# Motorcontroller.net
KiCad netlist of a schematic drawn in EAGLE
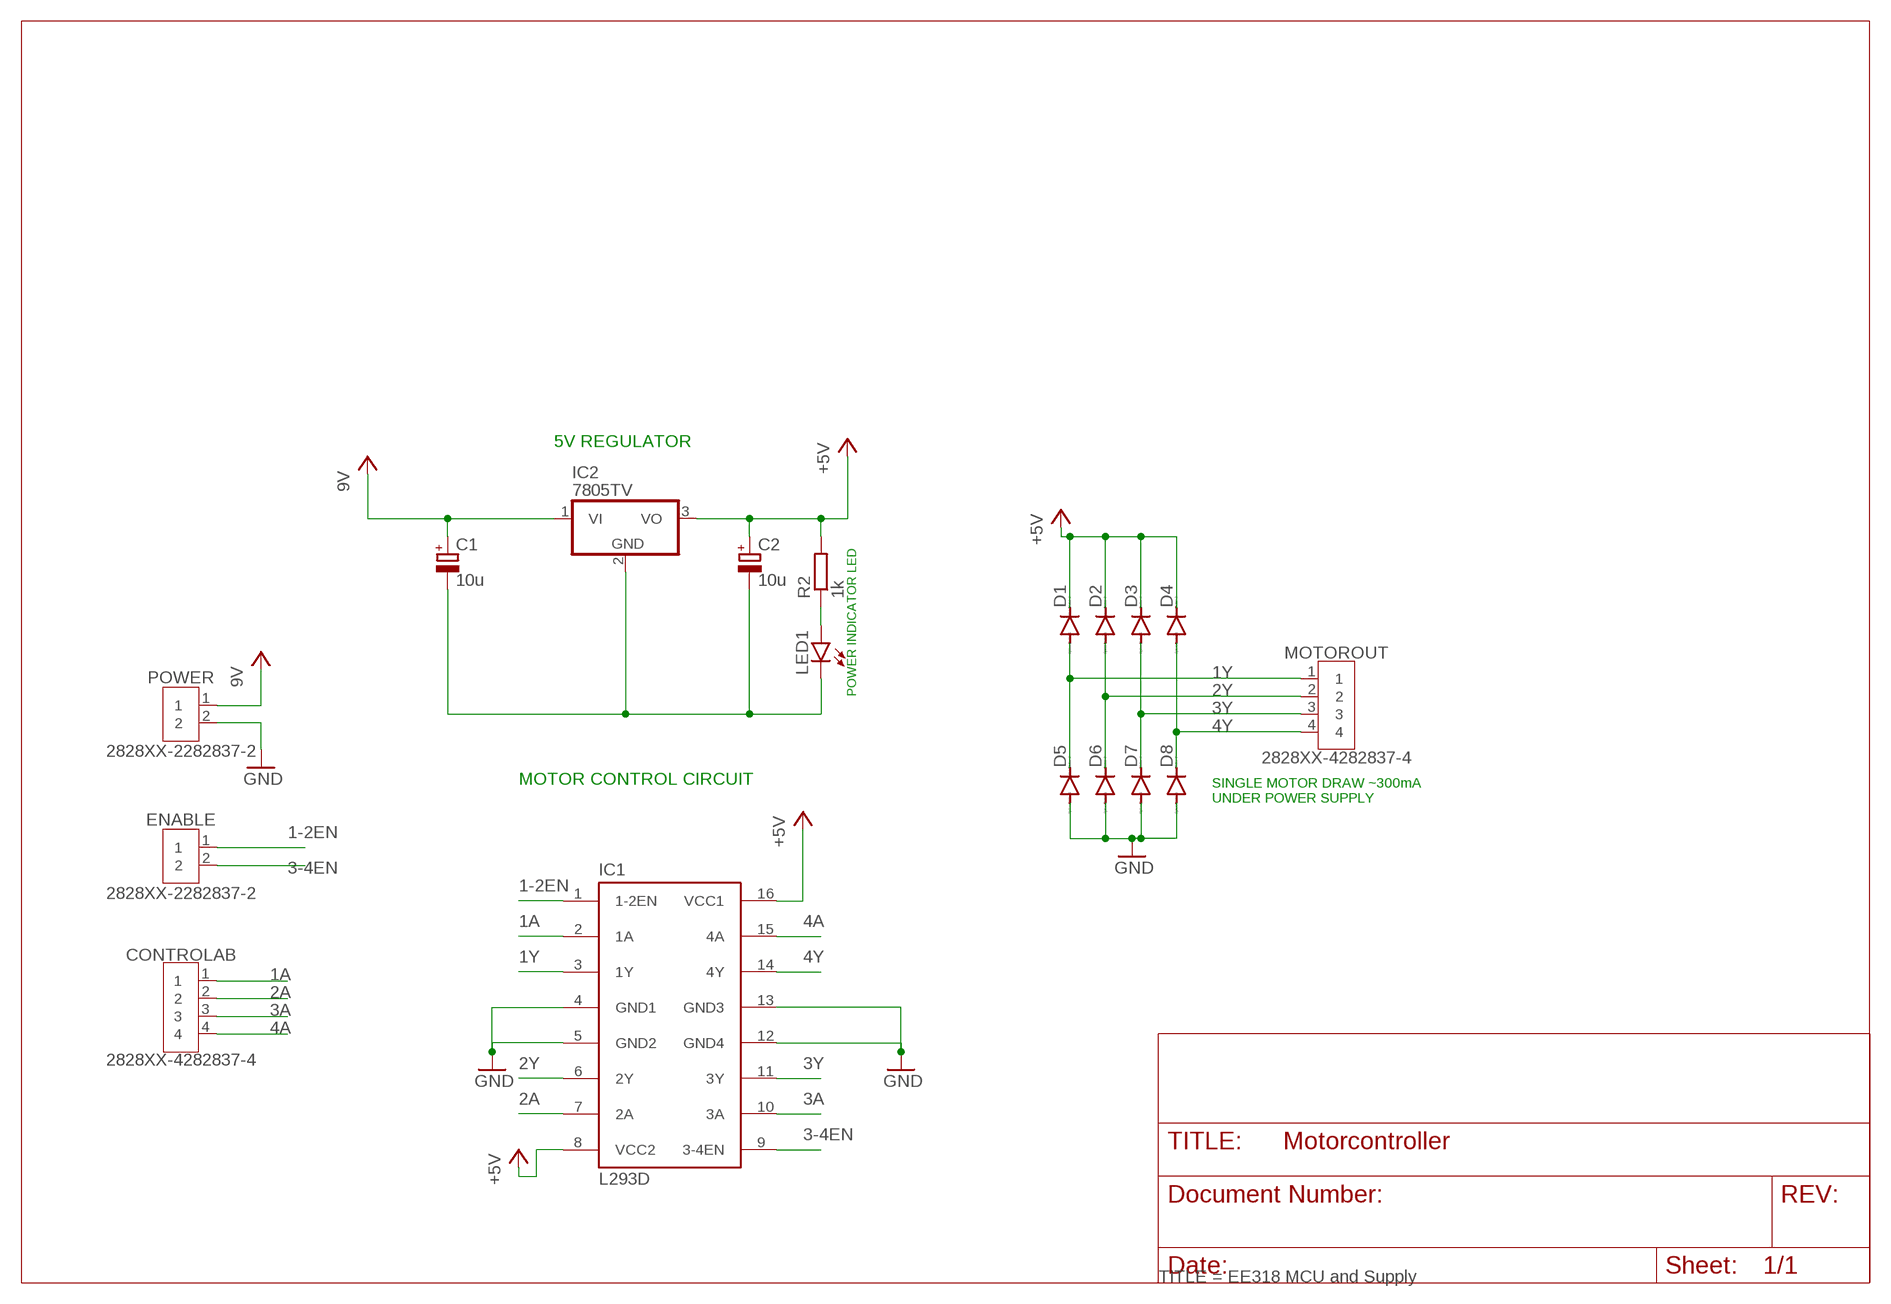
[diagram p0: schematic, sheet 1]

(export (version "E")
  (design (tool "Eeschema 10.0.6"))
  (components
    (comp (ref "C1")
      (value "10u")
      (footprint "eagle-import:E1,8-4")
      (libsource (lib "eagle-import") (part "CPOL-EUE1.8-4"))
    )
    (comp (ref "C2")
      (value "10u")
      (footprint "eagle-import:E1,8-4")
      (libsource (lib "eagle-import") (part "CPOL-EUE1.8-4"))
    )
    (comp (ref "CONTROLAB")
      (value "2828XX-4282837-4")
      (footprint "eagle-import:TERMBLK_508-4N")
      (fields (field (name "MANUFACTURER") "TE Connectivity AMP Connectors ") (field (name "MPN") "282837-4"))
      (libsource (lib "eagle-import") (part "2828XX-4282837-4"))
    )
    (comp (ref "D1")
      (value "DIODE-DO214AC")
      (footprint "eagle-import:DO214AC")
      (libsource (lib "eagle-import") (part "DIODE-DO214AC"))
    )
    (comp (ref "D2")
      (value "DIODE-DO214AC")
      (footprint "eagle-import:DO214AC")
      (libsource (lib "eagle-import") (part "DIODE-DO214AC"))
    )
    (comp (ref "D3")
      (value "DIODE-DO214AC")
      (footprint "eagle-import:DO214AC")
      (libsource (lib "eagle-import") (part "DIODE-DO214AC"))
    )
    (comp (ref "D4")
      (value "DIODE-DO214AC")
      (footprint "eagle-import:DO214AC")
      (libsource (lib "eagle-import") (part "DIODE-DO214AC"))
    )
    (comp (ref "D5")
      (value "DIODE-DO214AC")
      (footprint "eagle-import:DO214AC")
      (libsource (lib "eagle-import") (part "DIODE-DO214AC"))
    )
    (comp (ref "D6")
      (value "DIODE-DO214AC")
      (footprint "eagle-import:DO214AC")
      (libsource (lib "eagle-import") (part "DIODE-DO214AC"))
    )
    (comp (ref "D7")
      (value "DIODE-DO214AC")
      (footprint "eagle-import:DO214AC")
      (libsource (lib "eagle-import") (part "DIODE-DO214AC"))
    )
    (comp (ref "D8")
      (value "DIODE-DO214AC")
      (footprint "eagle-import:DO214AC")
      (libsource (lib "eagle-import") (part "DIODE-DO214AC"))
    )
    (comp (ref "ENABLE")
      (value "2828XX-2282837-2")
      (footprint "eagle-import:TERMBLK_508-2N")
      (fields (field (name "MANUFACTURER") "TE Connectivity") (field (name "MPN") "282837-2"))
      (libsource (lib "eagle-import") (part "2828XX-2282837-2"))
    )
    (comp (ref "IC1")
      (value "L293D")
      (footprint "eagle-import:DIL16")
      (libsource (lib "eagle-import") (part "L293D"))
    )
    (comp (ref "IC2")
      (value "7805TV")
      (footprint "eagle-import:TO220V")
      (libsource (lib "eagle-import") (part "78TV05"))
    )
    (comp (ref "LED1")
      (value "LED5MM")
      (footprint "eagle-import:LED5MM")
      (libsource (lib "eagle-import") (part "LED5MM"))
    )
    (comp (ref "MOTOROUT")
      (value "2828XX-4282837-4")
      (footprint "eagle-import:TERMBLK_508-4N")
      (fields (field (name "MANUFACTURER") "TE Connectivity AMP Connectors ") (field (name "MPN") "282837-4"))
      (libsource (lib "eagle-import") (part "2828XX-4282837-4"))
    )
    (comp (ref "POWER")
      (value "2828XX-2282837-2")
      (footprint "eagle-import:TERMBLK_508-2N")
      (fields (field (name "MANUFACTURER") "TE Connectivity") (field (name "MPN") "282837-2"))
      (libsource (lib "eagle-import") (part "2828XX-2282837-2"))
    )
    (comp (ref "R2")
      (value "1k")
      (footprint "eagle-import:R1206")
      (libsource (lib "eagle-import") (part "R-EU_R1206"))
    )
  )
  (nets
    (net (code "1") (name "+5V") (class "Default")
      (node (ref "C1") (pin "+") (pinfunction "+_+") (pintype "passive"))
      (node (ref "C2") (pin "+") (pinfunction "+_+") (pintype "passive"))
      (node (ref "D1") (pin "C") (pinfunction "C_C") (pintype "passive"))
      (node (ref "D2") (pin "C") (pinfunction "C_C") (pintype "passive"))
      (node (ref "D3") (pin "C") (pinfunction "C_C") (pintype "passive"))
      (node (ref "D4") (pin "C") (pinfunction "C_C") (pintype "passive"))
      (node (ref "IC1") (pin "16") (pinfunction "VCC1_16") (pintype "power_in"))
      (node (ref "IC1") (pin "8") (pinfunction "VCC2_8") (pintype "power_in"))
      (node (ref "IC2") (pin "1") (pinfunction "VI_1") (pintype "input"))
      (node (ref "IC2") (pin "3") (pinfunction "VO_3") (pintype "passive"))
      (node (ref "POWER") (pin "1") (pinfunction "1_1") (pintype "bidirectional"))
      (node (ref "R2") (pin "2") (pinfunction "2_2") (pintype "passive"))
    )
    (net (code "2") (name "/1-2EN") (class "Default")
      (node (ref "ENABLE") (pin "1") (pinfunction "1_1") (pintype "bidirectional"))
      (node (ref "IC1") (pin "1") (pinfunction "1-2EN_1") (pintype "input"))
    )
    (net (code "3") (name "/1A") (class "Default")
      (node (ref "CONTROLAB") (pin "1") (pinfunction "1_1") (pintype "bidirectional"))
      (node (ref "IC1") (pin "2") (pinfunction "1A_2") (pintype "input"))
    )
    (net (code "4") (name "/1Y") (class "Default")
      (node (ref "D1") (pin "A") (pinfunction "A_A") (pintype "passive"))
      (node (ref "D5") (pin "C") (pinfunction "C_C") (pintype "passive"))
      (node (ref "IC1") (pin "3") (pinfunction "1Y_3") (pintype "output"))
      (node (ref "MOTOROUT") (pin "1") (pinfunction "1_1") (pintype "bidirectional"))
    )
    (net (code "5") (name "/2A") (class "Default")
      (node (ref "CONTROLAB") (pin "2") (pinfunction "2_2") (pintype "bidirectional"))
      (node (ref "IC1") (pin "7") (pinfunction "2A_7") (pintype "input"))
    )
    (net (code "6") (name "/2Y") (class "Default")
      (node (ref "D2") (pin "A") (pinfunction "A_A") (pintype "passive"))
      (node (ref "D6") (pin "C") (pinfunction "C_C") (pintype "passive"))
      (node (ref "IC1") (pin "6") (pinfunction "2Y_6") (pintype "output"))
      (node (ref "MOTOROUT") (pin "2") (pinfunction "2_2") (pintype "bidirectional"))
    )
    (net (code "7") (name "/3-4EN") (class "Default")
      (node (ref "ENABLE") (pin "2") (pinfunction "2_2") (pintype "bidirectional"))
      (node (ref "IC1") (pin "9") (pinfunction "3-4EN_9") (pintype "input"))
    )
    (net (code "8") (name "/3A") (class "Default")
      (node (ref "CONTROLAB") (pin "3") (pinfunction "3_3") (pintype "bidirectional"))
      (node (ref "IC1") (pin "10") (pinfunction "3A_10") (pintype "input"))
    )
    (net (code "9") (name "/3Y") (class "Default")
      (node (ref "D3") (pin "A") (pinfunction "A_A") (pintype "passive"))
      (node (ref "D7") (pin "C") (pinfunction "C_C") (pintype "passive"))
      (node (ref "IC1") (pin "11") (pinfunction "3Y_11") (pintype "output"))
      (node (ref "MOTOROUT") (pin "3") (pinfunction "3_3") (pintype "bidirectional"))
    )
    (net (code "10") (name "/4A") (class "Default")
      (node (ref "CONTROLAB") (pin "4") (pinfunction "4_4") (pintype "bidirectional"))
      (node (ref "IC1") (pin "15") (pinfunction "4A_15") (pintype "input"))
    )
    (net (code "11") (name "/4Y") (class "Default")
      (node (ref "D4") (pin "A") (pinfunction "A_A") (pintype "passive"))
      (node (ref "D8") (pin "C") (pinfunction "C_C") (pintype "passive"))
      (node (ref "IC1") (pin "14") (pinfunction "4Y_14") (pintype "output"))
      (node (ref "MOTOROUT") (pin "4") (pinfunction "4_4") (pintype "bidirectional"))
    )
    (net (code "12") (name "GND") (class "Default")
      (node (ref "D5") (pin "A") (pinfunction "A_A") (pintype "passive"))
      (node (ref "D6") (pin "A") (pinfunction "A_A") (pintype "passive"))
      (node (ref "D7") (pin "A") (pinfunction "A_A") (pintype "passive"))
      (node (ref "D8") (pin "A") (pinfunction "A_A") (pintype "passive"))
      (node (ref "IC1") (pin "12") (pinfunction "GND4_12") (pintype "power_in"))
      (node (ref "IC1") (pin "13") (pinfunction "GND3_13") (pintype "power_in"))
      (node (ref "IC1") (pin "4") (pinfunction "GND1_4") (pintype "power_in"))
      (node (ref "IC1") (pin "5") (pinfunction "GND2_5") (pintype "power_in"))
      (node (ref "POWER") (pin "2") (pinfunction "2_2") (pintype "bidirectional"))
    )
    (net (code "13") (name "Net-(IC2-GND)") (class "Default")
      (node (ref "C1") (pin "-") (pinfunction "-_-") (pintype "passive"))
      (node (ref "C2") (pin "-") (pinfunction "-_-") (pintype "passive"))
      (node (ref "IC2") (pin "2") (pinfunction "GND_2") (pintype "passive"))
      (node (ref "LED1") (pin "K") (pinfunction "C_K") (pintype "passive"))
    )
    (net (code "14") (name "Net-(LED1-PadA)") (class "Default")
      (node (ref "LED1") (pin "A") (pinfunction "A_A") (pintype "passive"))
      (node (ref "R2") (pin "1") (pinfunction "1_1") (pintype "passive"))
    )
  )
)
